# Bus_Isolator.net
KiCad netlist of a schematic drawn in EAGLE
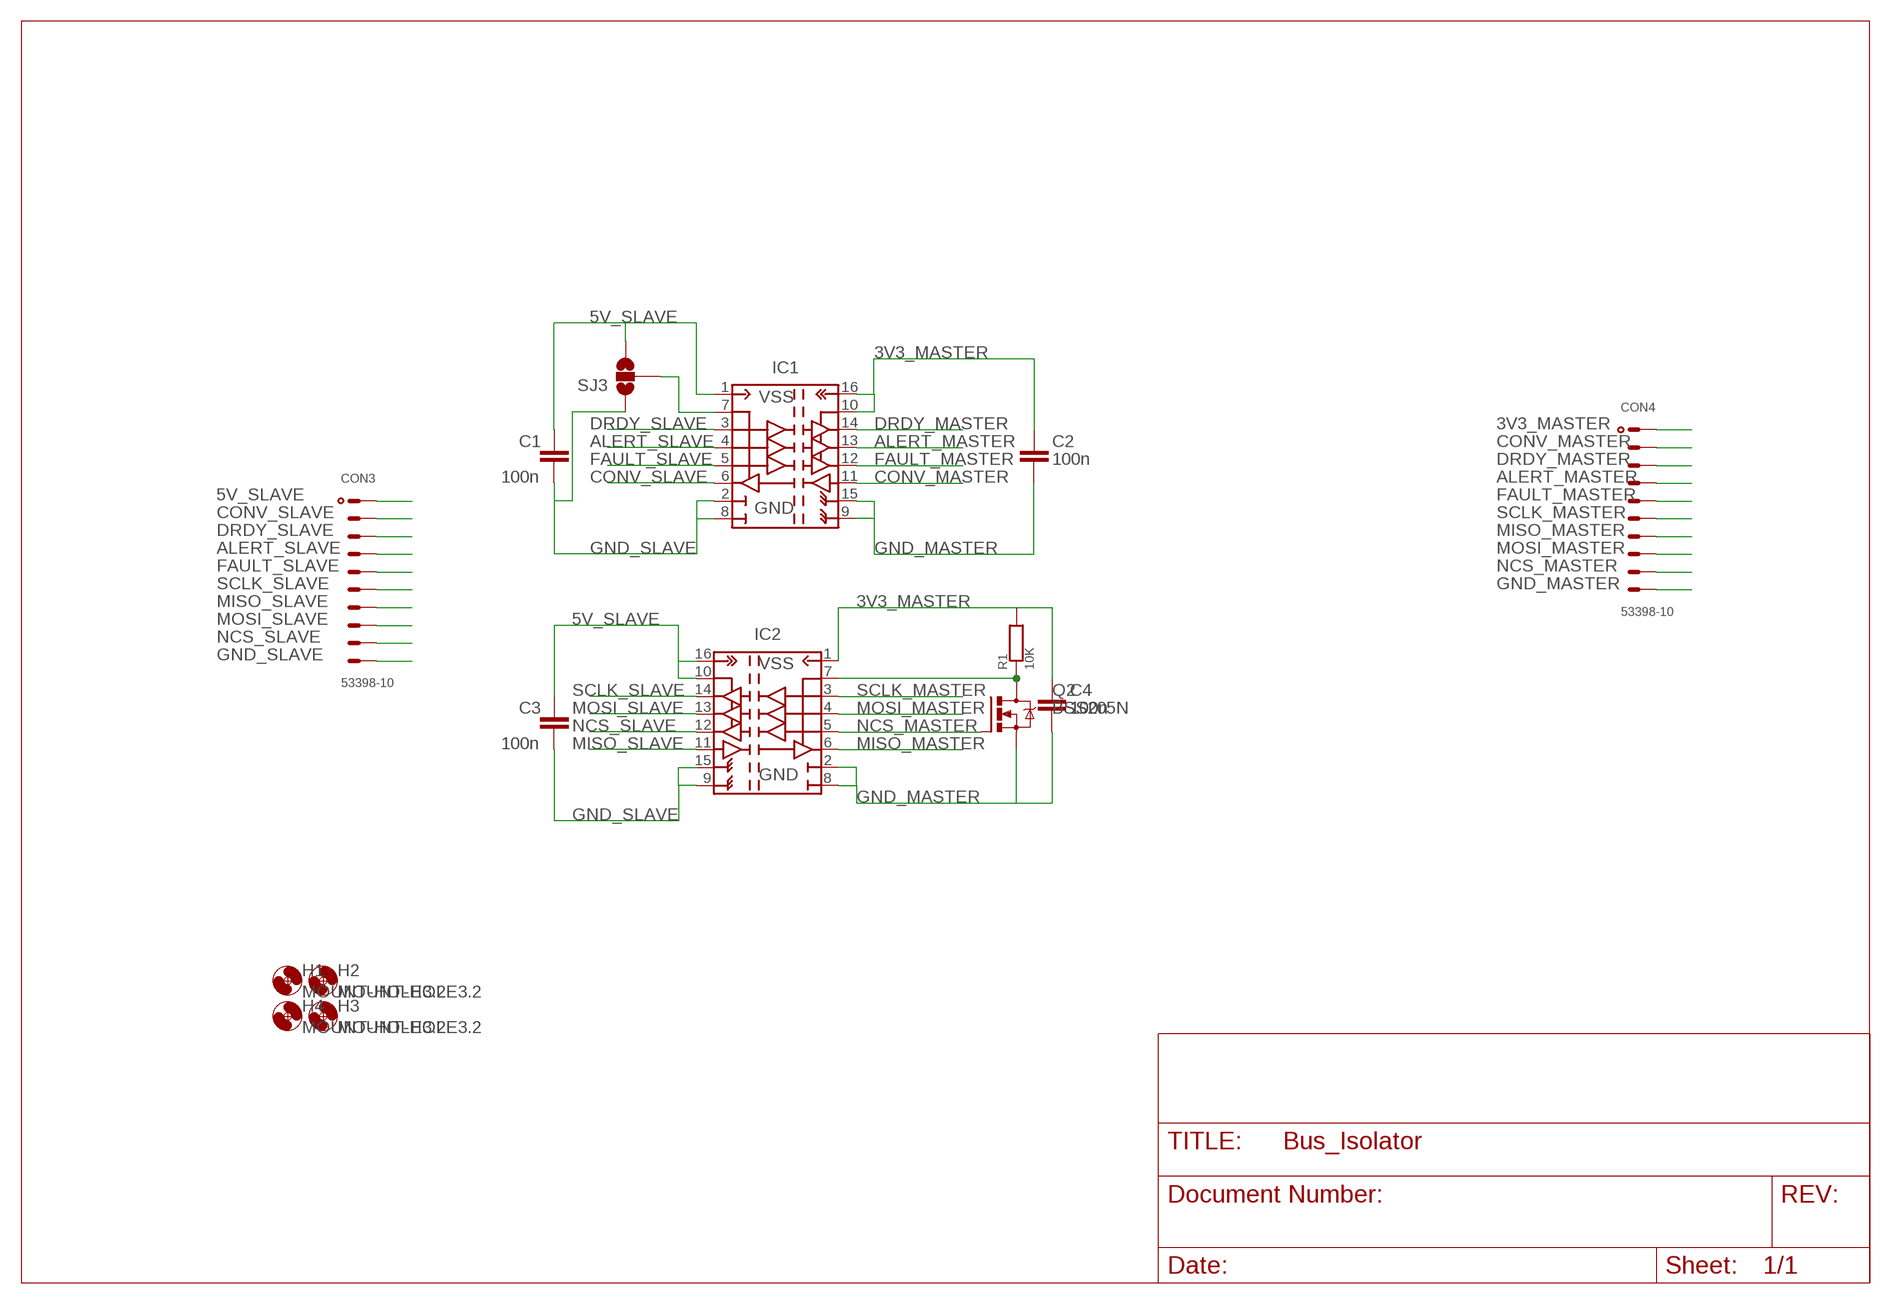
[diagram p0: schematic, sheet 1]

(export (version "E")
  (design (tool "Eeschema 10.0.6"))
  (components
    (comp (ref "C1")
      (value "100n")
      (footprint "eagle-import:C0805")
      (libsource (lib "eagle-import") (part "CSTD"))
    )
    (comp (ref "C2")
      (value "100n")
      (footprint "eagle-import:C0805")
      (libsource (lib "eagle-import") (part "CSTD"))
    )
    (comp (ref "C3")
      (value "100n")
      (footprint "eagle-import:C0805")
      (libsource (lib "eagle-import") (part "CSTD"))
    )
    (comp (ref "C4")
      (value "100n")
      (footprint "eagle-import:C0805")
      (libsource (lib "eagle-import") (part "CSTD"))
    )
    (comp (ref "CON3")
      (value "53398-10")
      (footprint "eagle-import:53398-10")
      (libsource (lib "eagle-import") (part "53?-10398"))
    )
    (comp (ref "CON4")
      (value "53398-10")
      (footprint "eagle-import:53398-10")
      (libsource (lib "eagle-import") (part "53?-10398"))
    )
    (comp (ref "H1")
      (value "MOUNT-HOLE3.2")
      (footprint "eagle-import:3,2")
      (libsource (lib "eagle-import") (part "MOUNT-HOLE3.2"))
    )
    (comp (ref "H2")
      (value "MOUNT-HOLE3.2")
      (footprint "eagle-import:3,2")
      (libsource (lib "eagle-import") (part "MOUNT-HOLE3.2"))
    )
    (comp (ref "H3")
      (value "MOUNT-HOLE3.2")
      (footprint "eagle-import:3,2")
      (libsource (lib "eagle-import") (part "MOUNT-HOLE3.2"))
    )
    (comp (ref "H4")
      (value "MOUNT-HOLE3.2")
      (footprint "eagle-import:3,2")
      (libsource (lib "eagle-import") (part "MOUNT-HOLE3.2"))
    )
    (comp (ref "IC1")
      (value "ISO7241")
      (footprint "eagle-import:R-PDSO-G16")
      (libsource (lib "eagle-import") (part "ISO7241"))
    )
    (comp (ref "IC2")
      (value "ISO7241")
      (footprint "eagle-import:R-PDSO-G16")
      (libsource (lib "eagle-import") (part "ISO7241"))
    )
    (comp (ref "Q2")
      (value "BSS205N")
      (footprint "eagle-import:SOT23")
      (libsource (lib "eagle-import") (part "BSS205N"))
    )
    (comp (ref "R1")
      (value "10K")
      (footprint "eagle-import:R0805")
      (libsource (lib "eagle-import") (part "R"))
    )
    (comp (ref "SJ3")
      (value "SOLDERJUMPER_2WAYS")
      (footprint "eagle-import:SJ_3")
      (libsource (lib "eagle-import") (part "SOLDERJUMPER_2WAYS"))
    )
  )
  (nets
    (net (code "1") (name "/3V3_MASTER") (class "Default")
      (node (ref "C2") (pin "2") (pinfunction "2_2") (pintype "passive"))
      (node (ref "C4") (pin "2") (pinfunction "2_2") (pintype "passive"))
      (node (ref "CON4") (pin "1") (pinfunction "1_1") (pintype "passive"))
      (node (ref "IC1") (pin "10") (pinfunction "EN2_10") (pintype "bidirectional"))
      (node (ref "IC1") (pin "16") (pinfunction "VCC2_16") (pintype "bidirectional"))
      (node (ref "IC2") (pin "1") (pinfunction "VCC1_1") (pintype "bidirectional"))
      (node (ref "R1") (pin "2") (pinfunction "2_2") (pintype "passive"))
    )
    (net (code "2") (name "/5V_SLAVE") (class "Default")
      (node (ref "C1") (pin "2") (pinfunction "2_2") (pintype "passive"))
      (node (ref "C3") (pin "2") (pinfunction "2_2") (pintype "passive"))
      (node (ref "CON3") (pin "1") (pinfunction "1_1") (pintype "passive"))
      (node (ref "IC1") (pin "1") (pinfunction "VCC1_1") (pintype "bidirectional"))
      (node (ref "IC2") (pin "10") (pinfunction "EN2_10") (pintype "bidirectional"))
      (node (ref "IC2") (pin "16") (pinfunction "VCC2_16") (pintype "bidirectional"))
      (node (ref "SJ3") (pin "3") (pinfunction "3_3") (pintype "passive"))
    )
    (net (code "3") (name "/ALERT_MASTER") (class "Default")
      (node (ref "CON4") (pin "4") (pinfunction "4_4") (pintype "passive"))
      (node (ref "IC1") (pin "13") (pinfunction "OUT_B_13") (pintype "bidirectional"))
    )
    (net (code "4") (name "/ALERT_SLAVE") (class "Default")
      (node (ref "CON3") (pin "4") (pinfunction "4_4") (pintype "passive"))
      (node (ref "IC1") (pin "4") (pinfunction "IN_B_4") (pintype "bidirectional"))
    )
    (net (code "5") (name "/CONV_MASTER") (class "Default")
      (node (ref "CON4") (pin "2") (pinfunction "2_2") (pintype "passive"))
      (node (ref "IC1") (pin "11") (pinfunction "IN_D_11") (pintype "bidirectional"))
    )
    (net (code "6") (name "/CONV_SLAVE") (class "Default")
      (node (ref "CON3") (pin "2") (pinfunction "2_2") (pintype "passive"))
      (node (ref "IC1") (pin "6") (pinfunction "OUT_D_6") (pintype "bidirectional"))
    )
    (net (code "7") (name "/DRDY_MASTER") (class "Default")
      (node (ref "CON4") (pin "3") (pinfunction "3_3") (pintype "passive"))
      (node (ref "IC1") (pin "14") (pinfunction "OUT_A_14") (pintype "bidirectional"))
    )
    (net (code "8") (name "/DRDY_SLAVE") (class "Default")
      (node (ref "CON3") (pin "3") (pinfunction "3_3") (pintype "passive"))
      (node (ref "IC1") (pin "3") (pinfunction "IN_A_3") (pintype "bidirectional"))
    )
    (net (code "9") (name "/FAULT_MASTER") (class "Default")
      (node (ref "CON4") (pin "5") (pinfunction "5_5") (pintype "passive"))
      (node (ref "IC1") (pin "12") (pinfunction "OUT_C_12") (pintype "bidirectional"))
    )
    (net (code "10") (name "/FAULT_SLAVE") (class "Default")
      (node (ref "CON3") (pin "5") (pinfunction "5_5") (pintype "passive"))
      (node (ref "IC1") (pin "5") (pinfunction "IN_C_5") (pintype "bidirectional"))
    )
    (net (code "11") (name "/GND_MASTER") (class "Default")
      (node (ref "C2") (pin "1") (pinfunction "1_1") (pintype "passive"))
      (node (ref "C4") (pin "1") (pinfunction "1_1") (pintype "passive"))
      (node (ref "CON4") (pin "10") (pinfunction "10_10") (pintype "passive"))
      (node (ref "IC1") (pin "15") (pinfunction "GND21_15") (pintype "bidirectional"))
      (node (ref "IC1") (pin "9") (pinfunction "GND22_9") (pintype "bidirectional"))
      (node (ref "IC2") (pin "2") (pinfunction "GND11_2") (pintype "bidirectional"))
      (node (ref "IC2") (pin "8") (pinfunction "GND12_8") (pintype "bidirectional"))
      (node (ref "Q2") (pin "2") (pinfunction "S_2") (pintype "passive"))
    )
    (net (code "12") (name "/GND_SLAVE") (class "Default")
      (node (ref "C1") (pin "1") (pinfunction "1_1") (pintype "passive"))
      (node (ref "C3") (pin "1") (pinfunction "1_1") (pintype "passive"))
      (node (ref "CON3") (pin "10") (pinfunction "10_10") (pintype "passive"))
      (node (ref "IC1") (pin "2") (pinfunction "GND11_2") (pintype "bidirectional"))
      (node (ref "IC1") (pin "8") (pinfunction "GND12_8") (pintype "bidirectional"))
      (node (ref "IC2") (pin "15") (pinfunction "GND21_15") (pintype "bidirectional"))
      (node (ref "IC2") (pin "9") (pinfunction "GND22_9") (pintype "bidirectional"))
      (node (ref "SJ3") (pin "1") (pinfunction "1_1") (pintype "passive"))
    )
    (net (code "13") (name "/MISO_MASTER") (class "Default")
      (node (ref "CON4") (pin "7") (pinfunction "7_7") (pintype "passive"))
      (node (ref "IC2") (pin "6") (pinfunction "OUT_D_6") (pintype "bidirectional"))
    )
    (net (code "14") (name "/MISO_SLAVE") (class "Default")
      (node (ref "CON3") (pin "7") (pinfunction "7_7") (pintype "passive"))
      (node (ref "IC2") (pin "11") (pinfunction "IN_D_11") (pintype "bidirectional"))
    )
    (net (code "15") (name "/MOSI_MASTER") (class "Default")
      (node (ref "CON4") (pin "8") (pinfunction "8_8") (pintype "passive"))
      (node (ref "IC2") (pin "4") (pinfunction "IN_B_4") (pintype "bidirectional"))
    )
    (net (code "16") (name "/MOSI_SLAVE") (class "Default")
      (node (ref "CON3") (pin "8") (pinfunction "8_8") (pintype "passive"))
      (node (ref "IC2") (pin "13") (pinfunction "OUT_B_13") (pintype "bidirectional"))
    )
    (net (code "17") (name "/NCS_MASTER") (class "Default")
      (node (ref "CON4") (pin "9") (pinfunction "9_9") (pintype "passive"))
      (node (ref "IC2") (pin "5") (pinfunction "IN_C_5") (pintype "bidirectional"))
      (node (ref "Q2") (pin "1") (pinfunction "G_1") (pintype "passive"))
    )
    (net (code "18") (name "/NCS_SLAVE") (class "Default")
      (node (ref "CON3") (pin "9") (pinfunction "9_9") (pintype "passive"))
      (node (ref "IC2") (pin "12") (pinfunction "OUT_C_12") (pintype "bidirectional"))
    )
    (net (code "19") (name "/SCLK_MASTER") (class "Default")
      (node (ref "CON4") (pin "6") (pinfunction "6_6") (pintype "passive"))
      (node (ref "IC2") (pin "3") (pinfunction "IN_A_3") (pintype "bidirectional"))
    )
    (net (code "20") (name "/SCLK_SLAVE") (class "Default")
      (node (ref "CON3") (pin "6") (pinfunction "6_6") (pintype "passive"))
      (node (ref "IC2") (pin "14") (pinfunction "OUT_A_14") (pintype "bidirectional"))
    )
    (net (code "21") (name "Net-(IC1-EN1)") (class "Default")
      (node (ref "IC1") (pin "7") (pinfunction "EN1_7") (pintype "bidirectional"))
      (node (ref "SJ3") (pin "2") (pinfunction "2_2") (pintype "passive"))
    )
    (net (code "22") (name "Net-(IC2-EN1)") (class "Default")
      (node (ref "IC2") (pin "7") (pinfunction "EN1_7") (pintype "bidirectional"))
      (node (ref "Q2") (pin "3") (pinfunction "D_3") (pintype "passive"))
      (node (ref "R1") (pin "1") (pinfunction "1_1") (pintype "passive"))
    )
  )
)
